# controller.net
KiCad netlist of a schematic drawn in EAGLE
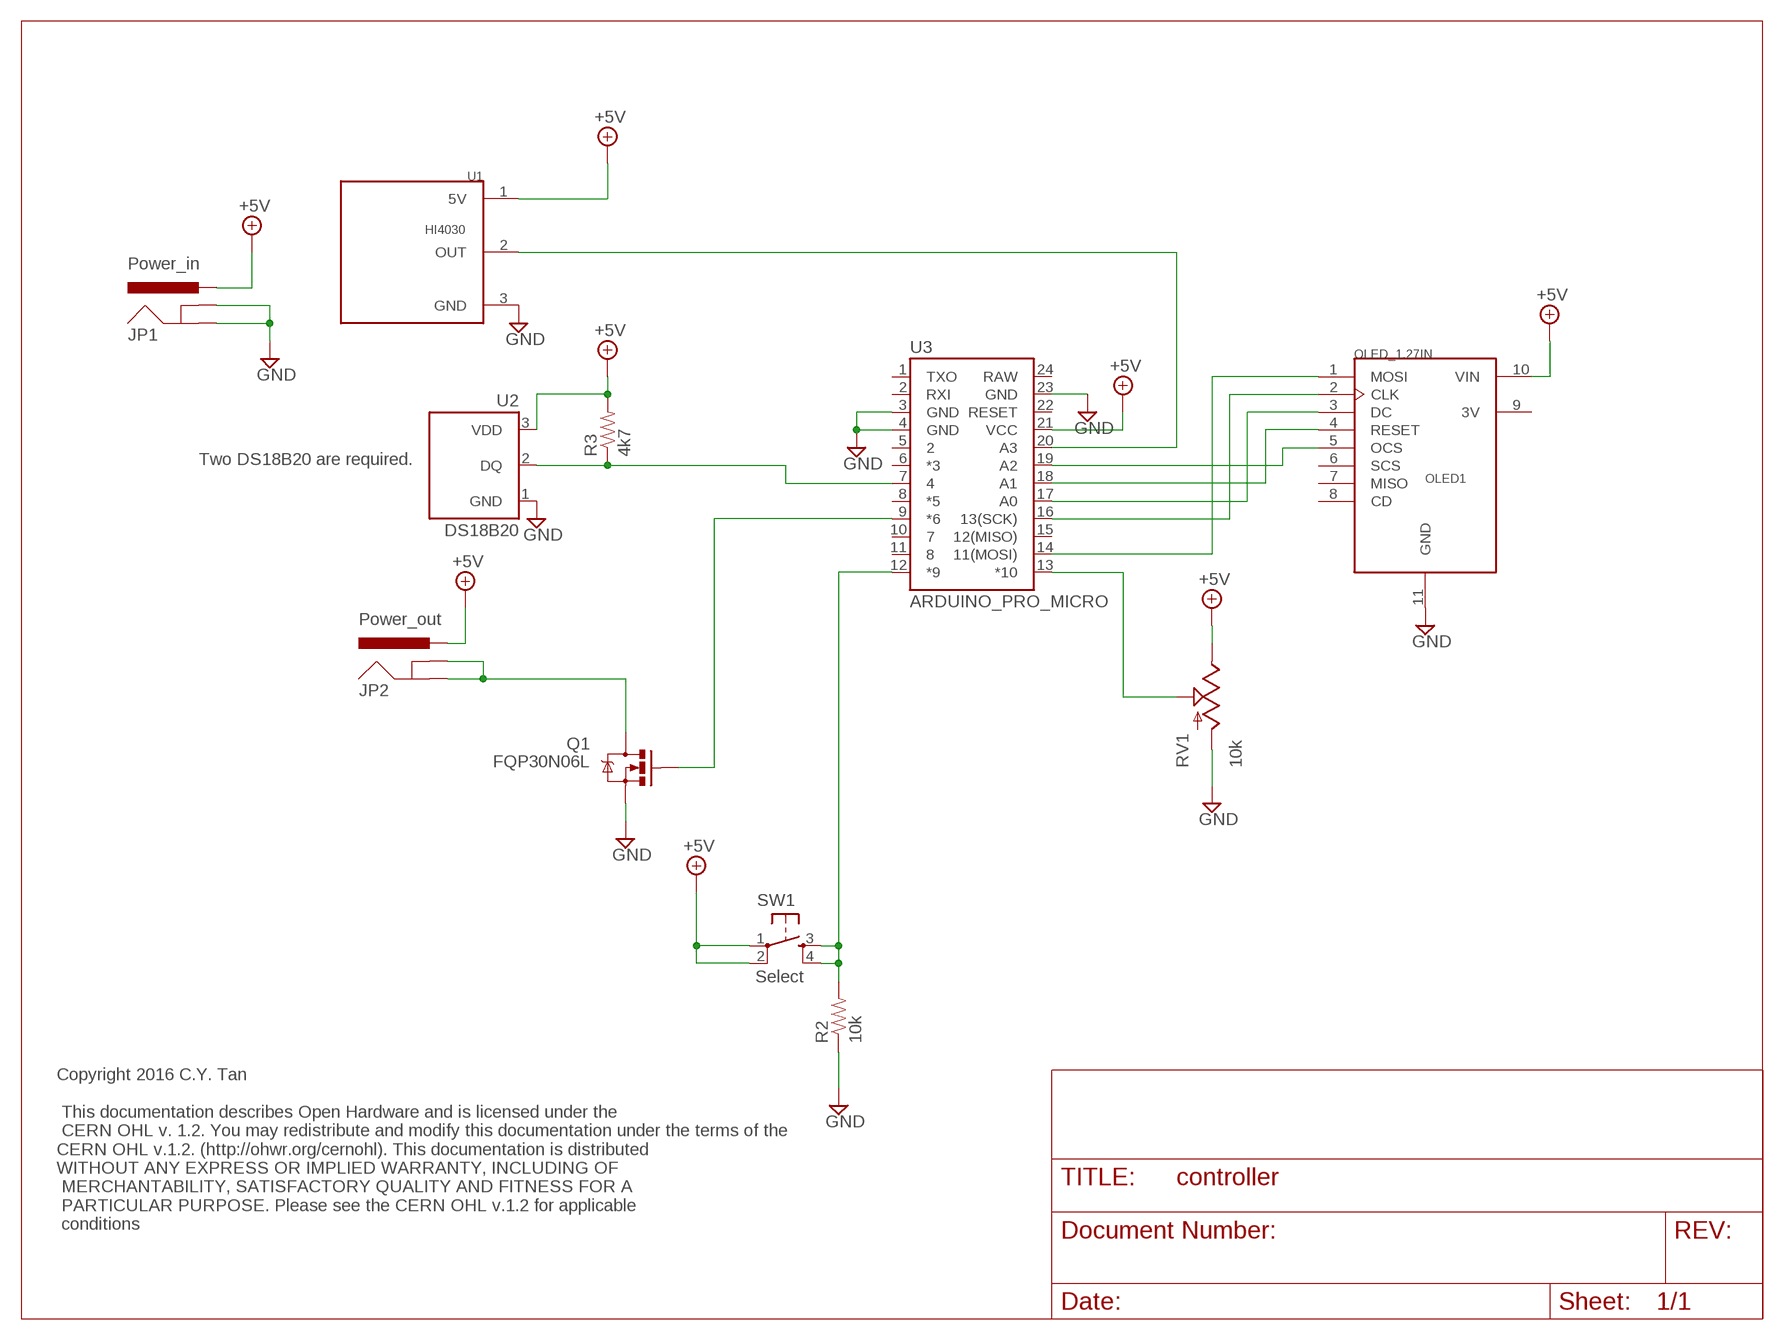
[diagram p0: schematic, sheet 1]

(export (version "E")
  (design (tool "Eeschema 10.0.6"))
  (components
    (comp (ref "JP1")
      (value "Power_in")
      (footprint "eagle-import:POWER_JACK_PTH")
      (libsource (lib "eagle-import") (part "POWER_JACKPTH"))
    )
    (comp (ref "JP2")
      (value "Power_out")
      (footprint "eagle-import:POWER_JACK_PTH")
      (libsource (lib "eagle-import") (part "POWER_JACKPTH"))
    )
    (comp (ref "OLED1")
      (value "OLED_1.27IN")
      (footprint "eagle-import:OLED_1.27INCH")
      (libsource (lib "eagle-import") (part "OLED_1.27IN"))
    )
    (comp (ref "Q1")
      (value "FQP30N06L")
      (footprint "eagle-import:TO220V")
      (libsource (lib "eagle-import") (part "MOSFET-NCHANNELFQP30N06L"))
    )
    (comp (ref "R2")
      (value "10k")
      (footprint "eagle-import:AXIAL-0.3")
      (libsource (lib "eagle-import") (part "RESISTORAXIAL-0.3"))
    )
    (comp (ref "R3")
      (value "4k7")
      (footprint "eagle-import:AXIAL-0.3")
      (libsource (lib "eagle-import") (part "RESISTORAXIAL-0.3"))
    )
    (comp (ref "RV1")
      (value "10k")
      (footprint "eagle-import:ALPS_POT_KIT")
      (libsource (lib "eagle-import") (part "POTALPS-KIT"))
    )
    (comp (ref "SW1")
      (value "Select")
      (footprint "eagle-import:TAC-SWITCH-PTH")
      (libsource (lib "eagle-import") (part "TACTILE-SWITCH-PTH"))
    )
    (comp (ref "U1")
      (value "HI4030")
      (footprint "eagle-import:1X03")
      (libsource (lib "eagle-import") (part "HUMIDITY_SENSOR"))
    )
    (comp (ref "U2")
      (value "DS18B20")
      (footprint "eagle-import:TO-92-AMMO")
      (libsource (lib "eagle-import") (part "DS18B20"))
    )
    (comp (ref "U3")
      (value "ARDUINO_PRO_MICRO")
      (footprint "eagle-import:ARDUINO_PRO_MICRO")
      (libsource (lib "eagle-import") (part "ARDUINO_PRO_MICRO"))
    )
  )
  (nets
    (net (code "1") (name "+5V") (class "Default")
      (node (ref "JP1") (pin "PWR") (pinfunction "PWR_PWR") (pintype "bidirectional"))
      (node (ref "JP2") (pin "PWR") (pinfunction "PWR_PWR") (pintype "bidirectional"))
      (node (ref "OLED1") (pin "10") (pinfunction "VIN_10") (pintype "power_in"))
      (node (ref "R3") (pin "P$2") (pinfunction "2_P$2") (pintype "passive"))
      (node (ref "RV1") (pin "P$1") (pinfunction "E_P$1") (pintype "passive"))
      (node (ref "SW1") (pin "1") (pinfunction "1_1") (pintype "passive"))
      (node (ref "SW1") (pin "2") (pinfunction "2_2") (pintype "passive"))
      (node (ref "U1") (pin "1") (pinfunction "5V_1") (pintype "power_in"))
      (node (ref "U2") (pin "3") (pinfunction "VDD_3") (pintype "power_in"))
      (node (ref "U3") (pin "21") (pinfunction "VCC_21") (pintype "bidirectional"))
    )
    (net (code "2") (name "/3V") (class "Default")
      (node (ref "OLED1") (pin "9") (pinfunction "3V_9") (pintype "power_in"))
    )
    (net (code "3") (name "GND") (class "Default")
      (node (ref "JP1") (pin "GND") (pinfunction "GND_GND") (pintype "bidirectional"))
      (node (ref "JP1") (pin "GNDBREAK") (pinfunction "GNDBREAK_GNDBREAK") (pintype "bidirectional"))
      (node (ref "OLED1") (pin "11") (pinfunction "GND_11") (pintype "power_in"))
      (node (ref "Q1") (pin "3") (pinfunction "S_3") (pintype "passive"))
      (node (ref "R2") (pin "P$1") (pinfunction "1_P$1") (pintype "passive"))
      (node (ref "RV1") (pin "P$3") (pinfunction "A_P$3") (pintype "passive"))
      (node (ref "U1") (pin "3") (pinfunction "GND_3") (pintype "power_in"))
      (node (ref "U2") (pin "1") (pinfunction "GND_1") (pintype "power_in"))
      (node (ref "U3") (pin "23") (pinfunction "GND_23") (pintype "bidirectional"))
      (node (ref "U3") (pin "3") (pinfunction "GND_3") (pintype "bidirectional"))
      (node (ref "U3") (pin "4") (pinfunction "GND_4") (pintype "bidirectional"))
    )
    (net (code "4") (name "Net-(OLED1-CLK)") (class "Default")
      (node (ref "OLED1") (pin "2") (pinfunction "CLK_2") (pintype "bidirectional"))
      (node (ref "U3") (pin "16") (pinfunction "13(SCK)_16") (pintype "bidirectional"))
    )
    (net (code "5") (name "Net-(OLED1-DC)") (class "Default")
      (node (ref "OLED1") (pin "3") (pinfunction "DC_3") (pintype "bidirectional"))
      (node (ref "U3") (pin "17") (pinfunction "A0_17") (pintype "bidirectional"))
    )
    (net (code "6") (name "Net-(OLED1-MOSI)") (class "Default")
      (node (ref "OLED1") (pin "1") (pinfunction "MOSI_1") (pintype "bidirectional"))
      (node (ref "U3") (pin "14") (pinfunction "11(MOSI)_14") (pintype "bidirectional"))
    )
    (net (code "7") (name "Net-(OLED1-OCS)") (class "Default")
      (node (ref "OLED1") (pin "5") (pinfunction "OCS_5") (pintype "bidirectional"))
      (node (ref "U3") (pin "19") (pinfunction "A2_19") (pintype "bidirectional"))
    )
    (net (code "8") (name "Net-(OLED1-RESET)") (class "Default")
      (node (ref "OLED1") (pin "4") (pinfunction "RESET_4") (pintype "input"))
      (node (ref "U3") (pin "18") (pinfunction "A1_18") (pintype "bidirectional"))
    )
    (net (code "9") (name "Net-(Q1-D)") (class "Default")
      (node (ref "JP2") (pin "GND") (pinfunction "GND_GND") (pintype "bidirectional"))
      (node (ref "JP2") (pin "GNDBREAK") (pinfunction "GNDBREAK_GNDBREAK") (pintype "bidirectional"))
      (node (ref "Q1") (pin "2") (pinfunction "D_2") (pintype "passive"))
    )
    (net (code "10") (name "Net-(Q1-G)") (class "Default")
      (node (ref "Q1") (pin "1") (pinfunction "G_1") (pintype "passive"))
      (node (ref "U3") (pin "9") (pinfunction "*6_9") (pintype "bidirectional"))
    )
    (net (code "11") (name "Net-(R2-2)") (class "Default")
      (node (ref "R2") (pin "P$2") (pinfunction "2_P$2") (pintype "passive"))
      (node (ref "SW1") (pin "3") (pinfunction "3_3") (pintype "passive"))
      (node (ref "SW1") (pin "4") (pinfunction "4_4") (pintype "passive"))
      (node (ref "U3") (pin "12") (pinfunction "*9_12") (pintype "bidirectional"))
    )
    (net (code "12") (name "Net-(R3-1)") (class "Default")
      (node (ref "R3") (pin "P$1") (pinfunction "1_P$1") (pintype "passive"))
      (node (ref "U2") (pin "2") (pinfunction "DQ_2") (pintype "bidirectional"))
      (node (ref "U3") (pin "7") (pinfunction "4_7") (pintype "bidirectional"))
    )
    (net (code "13") (name "Net-(RV1-S)") (class "Default")
      (node (ref "RV1") (pin "P$2") (pinfunction "S_P$2") (pintype "passive"))
      (node (ref "U3") (pin "13") (pinfunction "*10_13") (pintype "bidirectional"))
    )
    (net (code "14") (name "Net-(U1-OUT)") (class "Default")
      (node (ref "U1") (pin "2") (pinfunction "OUT_2") (pintype "output"))
      (node (ref "U3") (pin "20") (pinfunction "A3_20") (pintype "bidirectional"))
    )
    (net (code "15") (name "unconnected-(OLED1-CD-Pad8)") (class "Default")
      (node (ref "OLED1") (pin "8") (pinfunction "CD_8") (pintype "bidirectional"))
    )
    (net (code "16") (name "unconnected-(OLED1-MISO-Pad7)") (class "Default")
      (node (ref "OLED1") (pin "7") (pinfunction "MISO_7") (pintype "bidirectional"))
    )
    (net (code "17") (name "unconnected-(OLED1-SCS-Pad6)") (class "Default")
      (node (ref "OLED1") (pin "6") (pinfunction "SCS_6") (pintype "bidirectional"))
    )
    (net (code "18") (name "unconnected-(U3-*3-Pad6)") (class "Default")
      (node (ref "U3") (pin "6") (pinfunction "*3_6") (pintype "bidirectional"))
    )
    (net (code "19") (name "unconnected-(U3-*5-Pad8)") (class "Default")
      (node (ref "U3") (pin "8") (pinfunction "*5_8") (pintype "bidirectional"))
    )
    (net (code "20") (name "unconnected-(U3-2-Pad5)") (class "Default")
      (node (ref "U3") (pin "5") (pinfunction "2_5") (pintype "bidirectional"))
    )
    (net (code "21") (name "unconnected-(U3-7-Pad10)") (class "Default")
      (node (ref "U3") (pin "10") (pinfunction "7_10") (pintype "bidirectional"))
    )
    (net (code "22") (name "unconnected-(U3-8-Pad11)") (class "Default")
      (node (ref "U3") (pin "11") (pinfunction "8_11") (pintype "bidirectional"))
    )
    (net (code "23") (name "unconnected-(U3-12(MISO)-Pad15)") (class "Default")
      (node (ref "U3") (pin "15") (pinfunction "12(MISO)_15") (pintype "bidirectional"))
    )
    (net (code "24") (name "unconnected-(U3-RAW-Pad24)") (class "Default")
      (node (ref "U3") (pin "24") (pinfunction "RAW_24") (pintype "bidirectional"))
    )
    (net (code "25") (name "unconnected-(U3-RESET-Pad22)") (class "Default")
      (node (ref "U3") (pin "22") (pinfunction "RESET_22") (pintype "bidirectional"))
    )
    (net (code "26") (name "unconnected-(U3-RXI-Pad2)") (class "Default")
      (node (ref "U3") (pin "2") (pinfunction "RXI_2") (pintype "bidirectional"))
    )
    (net (code "27") (name "unconnected-(U3-TXO-Pad1)") (class "Default")
      (node (ref "U3") (pin "1") (pinfunction "TXO_1") (pintype "bidirectional"))
    )
  )
)
